# Adafruit_ESP8266_Feather.net
KiCad netlist of a schematic drawn in EAGLE
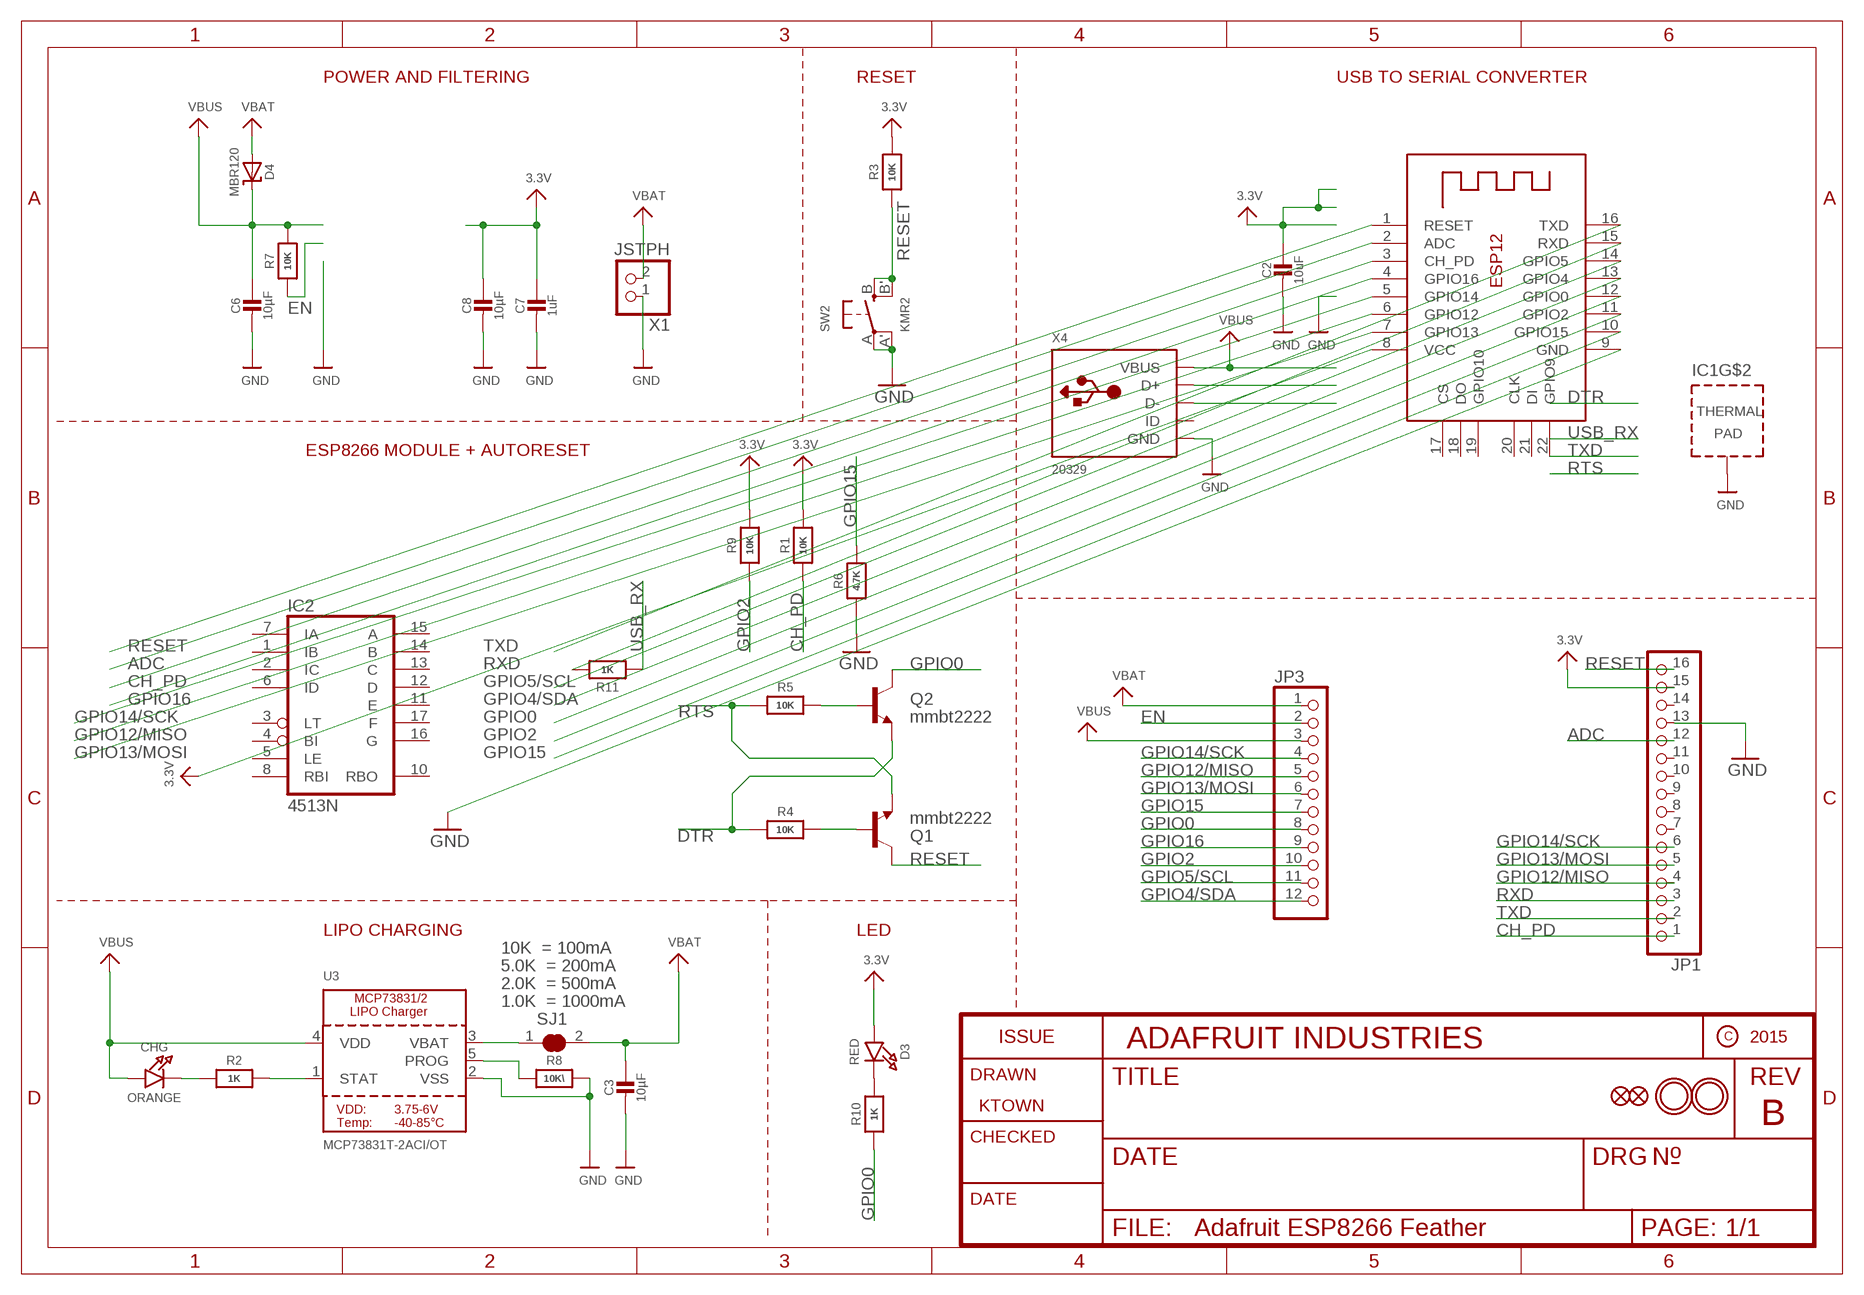
[diagram p0: schematic, sheet 1]

(export (version "E")
  (design (tool "Eeschema 10.0.6"))
  (components
    (comp (ref "C2")
      (value "10uF")
      (footprint "eagle-import:0805-NO")
      (libsource (lib "eagle-import") (part "CAP_CERAMIC0805-NOOUTLINE"))
    )
    (comp (ref "C3")
      (value "10µF")
      (footprint "eagle-import:0805-NO")
      (libsource (lib "eagle-import") (part "CAP_CERAMIC0805-NOOUTLINE"))
    )
    (comp (ref "C6")
      (value "10µF")
      (footprint "eagle-import:0805-NO")
      (libsource (lib "eagle-import") (part "CAP_CERAMIC0805-NOOUTLINE"))
    )
    (comp (ref "C7")
      (value "1uF")
      (footprint "eagle-import:0603-NO")
      (libsource (lib "eagle-import") (part "CAP_CERAMIC0603_NO"))
    )
    (comp (ref "C8")
      (value "10µF")
      (footprint "eagle-import:0805-NO")
      (libsource (lib "eagle-import") (part "CAP_CERAMIC0805-NOOUTLINE"))
    )
    (comp (ref "CHG")
      (value "ORANGE")
      (footprint "eagle-import:CHIPLED_0805_NOOUTLINE")
      (libsource (lib "eagle-import") (part "LED0805_NOOUTLINE"))
    )
    (comp (ref "D3")
      (value "RED")
      (footprint "eagle-import:CHIPLED_0805_NOOUTLINE")
      (libsource (lib "eagle-import") (part "LED0805_NOOUTLINE"))
    )
    (comp (ref "D4")
      (value "MBR120")
      (footprint "eagle-import:SOD-123")
      (libsource (lib "eagle-import") (part "DIODE-SCHOTTKYSOD-123"))
    )
    (comp (ref "IC1")
      (value "CP2104")
      (footprint "eagle-import:QFN24_4MM_SMSC")
      (libsource (lib "eagle-import") (part "CP2104"))
    )
    (comp (ref "IC2")
      (value "4513N")
      (footprint "eagle-import:DIL18")
      (libsource (lib "eagle-import") (part "4513N"))
    )
    (comp (ref "JP1")
      (value "HEADER-1X16ROUND")
      (footprint "eagle-import:1X16_ROUND")
      (libsource (lib "eagle-import") (part "HEADER-1X16ROUND"))
    )
    (comp (ref "JP3")
      (value "HEADER-1X12")
      (footprint "eagle-import:1X12_ROUND")
      (libsource (lib "eagle-import") (part "HEADER-1X12"))
    )
    (comp (ref "Q1")
      (value "mmbt2222")
      (footprint "eagle-import:SOT23-3")
      (libsource (lib "eagle-import") (part "TRANSISTOR_NPNSOT23-3"))
    )
    (comp (ref "Q2")
      (value "mmbt2222")
      (footprint "eagle-import:SOT23-3")
      (libsource (lib "eagle-import") (part "TRANSISTOR_NPNSOT23-3"))
    )
    (comp (ref "R1")
      (value "10K")
      (footprint "eagle-import:0603-NO")
      (libsource (lib "eagle-import") (part "RESISTOR_0603_NOOUT"))
    )
    (comp (ref "R2")
      (value "1K")
      (footprint "eagle-import:0603-NO")
      (libsource (lib "eagle-import") (part "RESISTOR_0603_NOOUT"))
    )
    (comp (ref "R3")
      (value "10K")
      (footprint "eagle-import:0603-NO")
      (libsource (lib "eagle-import") (part "RESISTOR_0603_NOOUT"))
    )
    (comp (ref "R4")
      (value "10K")
      (footprint "eagle-import:0603-NO")
      (libsource (lib "eagle-import") (part "RESISTOR_0603_NOOUT"))
    )
    (comp (ref "R5")
      (value "10K")
      (footprint "eagle-import:_0603MP")
      (libsource (lib "eagle-import") (part "RESISTOR_0603MP"))
    )
    (comp (ref "R6")
      (value "4.7K")
      (footprint "eagle-import:0603-NO")
      (libsource (lib "eagle-import") (part "RESISTOR_0603_NOOUT"))
    )
    (comp (ref "R7")
      (value "10K")
      (footprint "eagle-import:0603-NO")
      (libsource (lib "eagle-import") (part "RESISTOR_0603_NOOUT"))
    )
    (comp (ref "R8")
      (value "10K\\")
      (footprint "eagle-import:0603-NO")
      (libsource (lib "eagle-import") (part "RESISTOR_0603_NOOUT"))
    )
    (comp (ref "R9")
      (value "10K")
      (footprint "eagle-import:0603-NO")
      (libsource (lib "eagle-import") (part "RESISTOR_0603_NOOUT"))
    )
    (comp (ref "R10")
      (value "1K")
      (footprint "eagle-import:0603-NO")
      (libsource (lib "eagle-import") (part "RESISTOR_0603_NOOUT"))
    )
    (comp (ref "R11")
      (value "1K")
      (footprint "eagle-import:_0603MP")
      (libsource (lib "eagle-import") (part "RESISTOR_0603MP"))
    )
    (comp (ref "SJ1")
      (value "SOLDERJUMPER_CLOSED")
      (footprint "eagle-import:SOLDERJUMPER_CLOSEDWIRE")
      (libsource (lib "eagle-import") (part "SOLDERJUMPER_CLOSED"))
    )
    (comp (ref "SW2")
      (value "KMR2")
      (footprint "eagle-import:BTN_KMR2_4.6X2.8")
      (libsource (lib "eagle-import") (part "SWITCH_TACT_SMT4.6X2.8"))
    )
    (comp (ref "U$31")
      (value "MOUNTINGHOLE2.5")
      (footprint "eagle-import:MOUNTINGHOLE_2.5_PLATED")
      (libsource (lib "eagle-import") (part "MOUNTINGHOLE2.5"))
    )
    (comp (ref "U$32")
      (value "MOUNTINGHOLE2.5")
      (footprint "eagle-import:MOUNTINGHOLE_2.5_PLATED")
      (libsource (lib "eagle-import") (part "MOUNTINGHOLE2.5"))
    )
    (comp (ref "U$34")
      (value "FIDUCIAL\"\"")
      (footprint "eagle-import:FIDUCIAL_1MM")
      (libsource (lib "eagle-import") (part "FIDUCIAL{dblquote}{dblquote}"))
    )
    (comp (ref "U$35")
      (value "FIDUCIAL\"\"")
      (footprint "eagle-import:FIDUCIAL_1MM")
      (libsource (lib "eagle-import") (part "FIDUCIAL{dblquote}{dblquote}"))
    )
    (comp (ref "U3")
      (value "MCP73831T-2ACI/OT")
      (footprint "eagle-import:SOT23-5")
      (libsource (lib "eagle-import") (part "MCP73831/2"))
    )
    (comp (ref "X1")
      (value "JSTPH")
      (footprint "eagle-import:JSTPH2")
      (libsource (lib "eagle-import") (part "CON_JST_PH_2PIN"))
    )
    (comp (ref "X2")
      (value "ESP-12")
      (footprint "eagle-import:ESP-12E")
      (libsource (lib "eagle-import") (part "ESP-12E"))
    )
    (comp (ref "X4")
      (value "20329")
      (footprint "eagle-import:4UCONN_20329_V2")
      (libsource (lib "eagle-import") (part "USB_MICRO_20329_V2"))
    )
  )
  (nets
    (net (code "1") (name "/ADC") (class "Default")
      (node (ref "JP1") (pin "12") (pinfunction "12_12") (pintype "passive"))
      (node (ref "X2") (pin "2") (pinfunction "ADC_2") (pintype "passive"))
    )
    (net (code "2") (name "/CH_PD") (class "Default")
      (node (ref "JP1") (pin "1") (pinfunction "1_1") (pintype "passive"))
      (node (ref "R1") (pin "1") (pinfunction "1_1") (pintype "passive"))
      (node (ref "X2") (pin "3") (pinfunction "CH_PD_3") (pintype "input"))
    )
    (net (code "3") (name "/DTR") (class "Default")
      (node (ref "Q2") (pin "2") (pinfunction "E_2") (pintype "passive"))
      (node (ref "R4") (pin "1") (pinfunction "1_1") (pintype "passive"))
    )
    (net (code "4") (name "/EN") (class "Default")
      (node (ref "JP3") (pin "2") (pinfunction "2_2") (pintype "passive"))
      (node (ref "R7") (pin "1") (pinfunction "1_1") (pintype "passive"))
    )
    (net (code "5") (name "/GPIO0") (class "Default")
      (node (ref "JP3") (pin "8") (pinfunction "8_8") (pintype "passive"))
      (node (ref "Q2") (pin "3") (pinfunction "C_3") (pintype "passive"))
      (node (ref "R10") (pin "1") (pinfunction "1_1") (pintype "passive"))
      (node (ref "X2") (pin "12") (pinfunction "GPIO0_12") (pintype "bidirectional"))
    )
    (net (code "6") (name "/GPIO2") (class "Default")
      (node (ref "JP3") (pin "10") (pinfunction "10_10") (pintype "passive"))
      (node (ref "R9") (pin "1") (pinfunction "1_1") (pintype "passive"))
      (node (ref "X2") (pin "11") (pinfunction "GPIO2_11") (pintype "bidirectional"))
    )
    (net (code "7") (name "/GPIO4{slash}SDA") (class "Default")
      (node (ref "JP3") (pin "12") (pinfunction "12_12") (pintype "passive"))
      (node (ref "X2") (pin "13") (pinfunction "GPIO4_13") (pintype "bidirectional"))
    )
    (net (code "8") (name "/GPIO5{slash}SCL") (class "Default")
      (node (ref "JP3") (pin "11") (pinfunction "11_11") (pintype "passive"))
      (node (ref "X2") (pin "14") (pinfunction "GPIO5_14") (pintype "bidirectional"))
    )
    (net (code "9") (name "/GPIO12{slash}MISO") (class "Default")
      (node (ref "JP1") (pin "4") (pinfunction "4_4") (pintype "passive"))
      (node (ref "JP3") (pin "5") (pinfunction "5_5") (pintype "passive"))
      (node (ref "X2") (pin "6") (pinfunction "GPIO12_6") (pintype "bidirectional"))
    )
    (net (code "10") (name "/GPIO13{slash}MOSI") (class "Default")
      (node (ref "JP1") (pin "5") (pinfunction "5_5") (pintype "passive"))
      (node (ref "JP3") (pin "6") (pinfunction "6_6") (pintype "passive"))
      (node (ref "X2") (pin "7") (pinfunction "GPIO13_7") (pintype "bidirectional"))
    )
    (net (code "11") (name "/GPIO14{slash}SCK") (class "Default")
      (node (ref "JP1") (pin "6") (pinfunction "6_6") (pintype "passive"))
      (node (ref "JP3") (pin "4") (pinfunction "4_4") (pintype "passive"))
      (node (ref "X2") (pin "5") (pinfunction "GPIO14_5") (pintype "bidirectional"))
    )
    (net (code "12") (name "/GPIO15") (class "Default")
      (node (ref "JP3") (pin "7") (pinfunction "7_7") (pintype "passive"))
      (node (ref "R6") (pin "2") (pinfunction "2_2") (pintype "passive"))
      (node (ref "X2") (pin "10") (pinfunction "GPIO15_10") (pintype "bidirectional"))
    )
    (net (code "13") (name "/GPIO16") (class "Default")
      (node (ref "JP3") (pin "9") (pinfunction "9_9") (pintype "passive"))
      (node (ref "X2") (pin "4") (pinfunction "GPIO16_4") (pintype "bidirectional"))
    )
    (net (code "14") (name "/RESET") (class "Default")
      (node (ref "JP1") (pin "16") (pinfunction "16_16") (pintype "passive"))
      (node (ref "Q1") (pin "3") (pinfunction "C_3") (pintype "passive"))
      (node (ref "R3") (pin "1") (pinfunction "1_1") (pintype "passive"))
      (node (ref "SW2") (pin "B") (pinfunction "S_B") (pintype "passive"))
      (node (ref "SW2") (pin "B'") (pinfunction "S1_B'") (pintype "passive"))
      (node (ref "X2") (pin "1") (pinfunction "RESET_1") (pintype "input"))
    )
    (net (code "15") (name "/RTS") (class "Default")
      (node (ref "Q1") (pin "2") (pinfunction "E_2") (pintype "passive"))
      (node (ref "R5") (pin "1") (pinfunction "1_1") (pintype "passive"))
    )
    (net (code "16") (name "/RXD") (class "Default")
      (node (ref "JP1") (pin "3") (pinfunction "3_3") (pintype "passive"))
      (node (ref "R11") (pin "2") (pinfunction "2_2") (pintype "passive"))
      (node (ref "X2") (pin "15") (pinfunction "RXD_15") (pintype "input"))
    )
    (net (code "17") (name "/TXD") (class "Default")
      (node (ref "JP1") (pin "2") (pinfunction "2_2") (pintype "passive"))
      (node (ref "X2") (pin "16") (pinfunction "TXD_16") (pintype "output"))
      (node (ref "X2") (pin "22") (pinfunction "GPIO9_22") (pintype "bidirectional"))
    )
    (net (code "18") (name "/USB_RX") (class "Default")
      (node (ref "R11") (pin "1") (pinfunction "1_1") (pintype "passive"))
    )
    (net (code "19") (name "3.3V") (class "Default")
      (node (ref "C2") (pin "1") (pinfunction "1_1") (pintype "passive"))
      (node (ref "C7") (pin "1") (pinfunction "1_1") (pintype "passive"))
      (node (ref "C8") (pin "1") (pinfunction "1_1") (pintype "passive"))
      (node (ref "D3") (pin "A") (pinfunction "A_A") (pintype "passive"))
      (node (ref "JP1") (pin "15") (pinfunction "15_15") (pintype "passive"))
      (node (ref "R1") (pin "2") (pinfunction "2_2") (pintype "passive"))
      (node (ref "R3") (pin "2") (pinfunction "2_2") (pintype "passive"))
      (node (ref "R9") (pin "2") (pinfunction "2_2") (pintype "passive"))
      (node (ref "X2") (pin "8") (pinfunction "VCC_8") (pintype "power_in"))
    )
    (net (code "20") (name "GND") (class "Default")
      (node (ref "C2") (pin "2") (pinfunction "2_2") (pintype "passive"))
      (node (ref "C3") (pin "2") (pinfunction "2_2") (pintype "passive"))
      (node (ref "C6") (pin "2") (pinfunction "2_2") (pintype "passive"))
      (node (ref "C7") (pin "2") (pinfunction "2_2") (pintype "passive"))
      (node (ref "C8") (pin "2") (pinfunction "2_2") (pintype "passive"))
      (node (ref "IC1") (pin "THERM") (pinfunction "TP_THERM") (pintype "power_in"))
      (node (ref "JP1") (pin "13") (pinfunction "13_13") (pintype "passive"))
      (node (ref "R6") (pin "1") (pinfunction "1_1") (pintype "passive"))
      (node (ref "R8") (pin "2") (pinfunction "2_2") (pintype "passive"))
      (node (ref "SW2") (pin "A") (pinfunction "P_A") (pintype "passive"))
      (node (ref "SW2") (pin "A'") (pinfunction "P1_A'") (pintype "passive"))
      (node (ref "U3") (pin "2") (pinfunction "VSS_2") (pintype "power_in"))
      (node (ref "X1") (pin "1") (pinfunction "1_1") (pintype "passive"))
      (node (ref "X2") (pin "9") (pinfunction "GND_9") (pintype "power_in"))
      (node (ref "X4") (pin "BASE@1") (pinfunction "GND_BASE@1") (pintype "power_in"))
      (node (ref "X4") (pin "BASE@2") (pinfunction "GND_BASE@2") (pintype "power_in"))
      (node (ref "X4") (pin "GND") (pinfunction "GND_GND") (pintype "power_in"))
      (node (ref "X4") (pin "SPRT@1") (pinfunction "GND_SPRT@1") (pintype "power_in"))
      (node (ref "X4") (pin "SPRT@2") (pinfunction "GND_SPRT@2") (pintype "power_in"))
      (node (ref "X4") (pin "SPRT@3") (pinfunction "GND_SPRT@3") (pintype "power_in"))
      (node (ref "X4") (pin "SPRT@4") (pinfunction "GND_SPRT@4") (pintype "power_in"))
    )
    (net (code "21") (name "Net-(CHG-PadC)") (class "Default")
      (node (ref "CHG") (pin "C") (pinfunction "C_C") (pintype "passive"))
      (node (ref "R2") (pin "1") (pinfunction "1_1") (pintype "passive"))
    )
    (net (code "22") (name "Net-(D3-PadC)") (class "Default")
      (node (ref "D3") (pin "C") (pinfunction "C_C") (pintype "passive"))
      (node (ref "R10") (pin "2") (pinfunction "2_2") (pintype "passive"))
    )
    (net (code "23") (name "Net-(Q1-B)") (class "Default")
      (node (ref "Q1") (pin "1") (pinfunction "B_1") (pintype "passive"))
      (node (ref "R4") (pin "2") (pinfunction "2_2") (pintype "passive"))
    )
    (net (code "24") (name "Net-(Q2-B)") (class "Default")
      (node (ref "Q2") (pin "1") (pinfunction "B_1") (pintype "passive"))
      (node (ref "R5") (pin "2") (pinfunction "2_2") (pintype "passive"))
    )
    (net (code "25") (name "Net-(U3-PROG)") (class "Default")
      (node (ref "R8") (pin "1") (pinfunction "1_1") (pintype "passive"))
      (node (ref "U3") (pin "5") (pinfunction "PROG_5") (pintype "input"))
    )
    (net (code "26") (name "Net-(U3-STAT)") (class "Default")
      (node (ref "R2") (pin "2") (pinfunction "2_2") (pintype "passive"))
      (node (ref "U3") (pin "1") (pinfunction "STAT_1") (pintype "output"))
    )
    (net (code "27") (name "Net-(U3-VBAT)") (class "Default")
      (node (ref "SJ1") (pin "1") (pinfunction "1_1") (pintype "passive"))
      (node (ref "U3") (pin "3") (pinfunction "VBAT_3") (pintype "power_in"))
    )
    (net (code "28") (name "VBAT") (class "Default")
      (node (ref "C3") (pin "1") (pinfunction "1_1") (pintype "passive"))
      (node (ref "D4") (pin "A") (pinfunction "A_A") (pintype "passive"))
      (node (ref "JP3") (pin "1") (pinfunction "1_1") (pintype "passive"))
      (node (ref "SJ1") (pin "2") (pinfunction "2_2") (pintype "passive"))
      (node (ref "X1") (pin "2") (pinfunction "2_2") (pintype "passive"))
    )
    (net (code "29") (name "VBUS") (class "Default")
      (node (ref "C6") (pin "1") (pinfunction "1_1") (pintype "passive"))
      (node (ref "CHG") (pin "A") (pinfunction "A_A") (pintype "passive"))
      (node (ref "D4") (pin "C") (pinfunction "C_C") (pintype "passive"))
      (node (ref "JP3") (pin "3") (pinfunction "3_3") (pintype "passive"))
      (node (ref "R7") (pin "2") (pinfunction "2_2") (pintype "passive"))
      (node (ref "U3") (pin "4") (pinfunction "VDD_4") (pintype "power_in"))
      (node (ref "X4") (pin "VBUS") (pinfunction "VBUS_VBUS") (pintype "power_in"))
    )
    (net (code "30") (name "unconnected-(IC2A-A-Pad15)") (class "Default")
      (node (ref "IC2") (pin "15") (pinfunction "A_15") (pintype "output"))
    )
    (net (code "31") (name "unconnected-(IC2A-B-Pad14)") (class "Default")
      (node (ref "IC2") (pin "14") (pinfunction "B_14") (pintype "output"))
    )
    (net (code "32") (name "unconnected-(IC2A-BI-Pad4)") (class "Default")
      (node (ref "IC2") (pin "4") (pinfunction "BI_4") (pintype "input"))
    )
    (net (code "33") (name "unconnected-(IC2A-C-Pad13)") (class "Default")
      (node (ref "IC2") (pin "13") (pinfunction "C_13") (pintype "output"))
    )
    (net (code "34") (name "unconnected-(IC2A-D-Pad12)") (class "Default")
      (node (ref "IC2") (pin "12") (pinfunction "D_12") (pintype "output"))
    )
    (net (code "35") (name "unconnected-(IC2A-E-Pad11)") (class "Default")
      (node (ref "IC2") (pin "11") (pinfunction "E_11") (pintype "output"))
    )
    (net (code "36") (name "unconnected-(IC2A-F-Pad17)") (class "Default")
      (node (ref "IC2") (pin "17") (pinfunction "F_17") (pintype "output"))
    )
    (net (code "37") (name "unconnected-(IC2A-G-Pad16)") (class "Default")
      (node (ref "IC2") (pin "16") (pinfunction "G_16") (pintype "output"))
    )
    (net (code "38") (name "unconnected-(IC2A-IA-Pad7)") (class "Default")
      (node (ref "IC2") (pin "7") (pinfunction "IA_7") (pintype "input"))
    )
    (net (code "39") (name "unconnected-(IC2A-IB-Pad1)") (class "Default")
      (node (ref "IC2") (pin "1") (pinfunction "IB_1") (pintype "input"))
    )
    (net (code "40") (name "unconnected-(IC2A-IC-Pad2)") (class "Default")
      (node (ref "IC2") (pin "2") (pinfunction "IC_2") (pintype "input"))
    )
    (net (code "41") (name "unconnected-(IC2A-ID-Pad6)") (class "Default")
      (node (ref "IC2") (pin "6") (pinfunction "ID_6") (pintype "input"))
    )
    (net (code "42") (name "unconnected-(IC2A-LE-Pad5)") (class "Default")
      (node (ref "IC2") (pin "5") (pinfunction "LE_5") (pintype "input"))
    )
    (net (code "43") (name "unconnected-(IC2A-LT-Pad3)") (class "Default")
      (node (ref "IC2") (pin "3") (pinfunction "LT_3") (pintype "input"))
    )
    (net (code "44") (name "unconnected-(IC2A-RBI-Pad8)") (class "Default")
      (node (ref "IC2") (pin "8") (pinfunction "RBI_8") (pintype "input"))
    )
    (net (code "45") (name "unconnected-(IC2A-RBO-Pad10)") (class "Default")
      (node (ref "IC2") (pin "10") (pinfunction "RBO_10") (pintype "output"))
    )
    (net (code "46") (name "unconnected-(JP1-Pad7)") (class "Default")
      (node (ref "JP1") (pin "7") (pinfunction "7_7") (pintype "passive"))
    )
    (net (code "47") (name "unconnected-(JP1-Pad8)") (class "Default")
      (node (ref "JP1") (pin "8") (pinfunction "8_8") (pintype "passive"))
    )
    (net (code "48") (name "unconnected-(JP1-Pad9)") (class "Default")
      (node (ref "JP1") (pin "9") (pinfunction "9_9") (pintype "passive"))
    )
    (net (code "49") (name "unconnected-(JP1-Pad10)") (class "Default")
      (node (ref "JP1") (pin "10") (pinfunction "10_10") (pintype "passive"))
    )
    (net (code "50") (name "unconnected-(JP1-Pad11)") (class "Default")
      (node (ref "JP1") (pin "11") (pinfunction "11_11") (pintype "passive"))
    )
    (net (code "51") (name "unconnected-(JP1-Pad14)") (class "Default")
      (node (ref "JP1") (pin "14") (pinfunction "14_14") (pintype "passive"))
    )
    (net (code "52") (name "unconnected-(X2-CLK-Pad20)") (class "Default")
      (node (ref "X2") (pin "20") (pinfunction "CLK_20") (pintype "bidirectional"))
    )
    (net (code "53") (name "unconnected-(X2-CS-Pad17)") (class "Default")
      (node (ref "X2") (pin "17") (pinfunction "CS_17") (pintype "bidirectional"))
    )
    (net (code "54") (name "unconnected-(X2-DI-Pad21)") (class "Default")
      (node (ref "X2") (pin "21") (pinfunction "DI_21") (pintype "bidirectional"))
    )
    (net (code "55") (name "unconnected-(X2-DO-Pad18)") (class "Default")
      (node (ref "X2") (pin "18") (pinfunction "DO_18") (pintype "bidirectional"))
    )
    (net (code "56") (name "unconnected-(X2-GPIO10-Pad19)") (class "Default")
      (node (ref "X2") (pin "19") (pinfunction "GPIO10_19") (pintype "bidirectional"))
    )
    (net (code "57") (name "unconnected-(X4-PadD+)") (class "Default")
      (node (ref "X4") (pin "D+") (pinfunction "D+_D+") (pintype "bidirectional"))
    )
    (net (code "58") (name "unconnected-(X4-PadD-)") (class "Default")
      (node (ref "X4") (pin "D-") (pinfunction "D-_D-") (pintype "bidirectional"))
    )
    (net (code "59") (name "unconnected-(X4-PadID)") (class "Default")
      (node (ref "X4") (pin "ID") (pinfunction "ID_ID") (pintype "bidirectional"))
    )
  )
)
